# MOTO1.net
KiCad netlist of a schematic drawn in Altium Designer
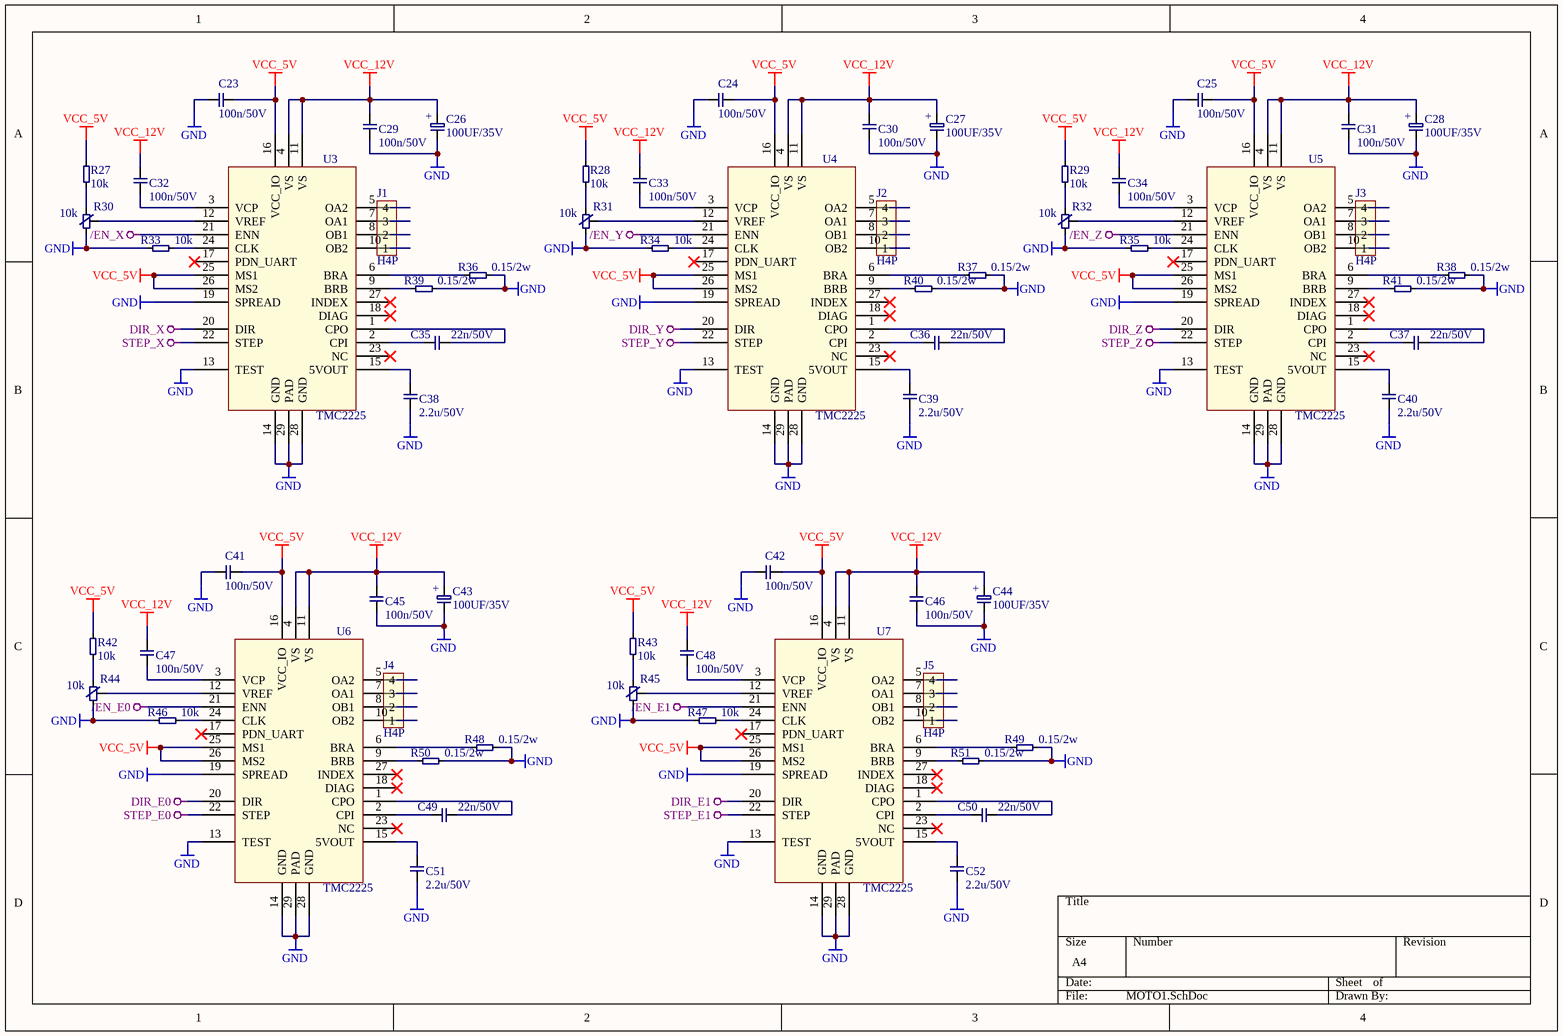
[diagram p0: MOTO1.SchDoc]

(export (version "E")
  (design (tool "Eeschema 10.0.6"))
  (components
    (comp (ref "C23")
      (value "100n/50V")
      (footprint "C0603(1608)")
      (libsource (lib "Fc_Integrated_Library") (part "Caps"))
    )
    (comp (ref "C24")
      (value "100n/50V")
      (footprint "C0603(1608)")
      (libsource (lib "Fc_Integrated_Library") (part "Caps"))
    )
    (comp (ref "C25")
      (value "100n/50V")
      (footprint "C0603(1608)")
      (libsource (lib "Fc_Integrated_Library") (part "Caps"))
    )
    (comp (ref "C26")
      (value "100UF/35V")
      (footprint "C6.3x7.7贴片铝电解电容")
      (libsource (lib "Fc_Integrated_Library") (part "Capsp"))
    )
    (comp (ref "C27")
      (value "100UF/35V")
      (footprint "C6.3x7.7贴片铝电解电容")
      (libsource (lib "Fc_Integrated_Library") (part "Capsp"))
    )
    (comp (ref "C28")
      (value "100UF/35V")
      (footprint "C6.3x7.7贴片铝电解电容")
      (libsource (lib "Fc_Integrated_Library") (part "Capsp"))
    )
    (comp (ref "C29")
      (value "100n/50V")
      (footprint "C0603(1608)")
      (libsource (lib "Fc_Integrated_Library") (part "Caps"))
    )
    (comp (ref "C30")
      (value "100n/50V")
      (footprint "C0603(1608)")
      (libsource (lib "Fc_Integrated_Library") (part "Caps"))
    )
    (comp (ref "C31")
      (value "100n/50V")
      (footprint "C0603(1608)")
      (libsource (lib "Fc_Integrated_Library") (part "Caps"))
    )
    (comp (ref "C32")
      (value "100n/50V")
      (footprint "C0603(1608)")
      (libsource (lib "Fc_Integrated_Library") (part "Caps"))
    )
    (comp (ref "C33")
      (value "100n/50V")
      (footprint "C0603(1608)")
      (libsource (lib "Fc_Integrated_Library") (part "Caps"))
    )
    (comp (ref "C34")
      (value "100n/50V")
      (footprint "C0603(1608)")
      (libsource (lib "Fc_Integrated_Library") (part "Caps"))
    )
    (comp (ref "C35")
      (value "22n/50V")
      (footprint "C0603(1608)")
      (libsource (lib "Fc_Integrated_Library") (part "Caps"))
    )
    (comp (ref "C36")
      (value "22n/50V")
      (footprint "C0603(1608)")
      (libsource (lib "Fc_Integrated_Library") (part "Caps"))
    )
    (comp (ref "C37")
      (value "22n/50V")
      (footprint "C0603(1608)")
      (libsource (lib "Fc_Integrated_Library") (part "Caps"))
    )
    (comp (ref "C38")
      (value "2.2u/50V")
      (footprint "C0805(2012)")
      (libsource (lib "Fc_Integrated_Library") (part "Caps"))
    )
    (comp (ref "C39")
      (value "2.2u/50V")
      (footprint "C0805(2012)")
      (libsource (lib "Fc_Integrated_Library") (part "Caps"))
    )
    (comp (ref "C40")
      (value "2.2u/50V")
      (footprint "C0805(2012)")
      (libsource (lib "Fc_Integrated_Library") (part "Caps"))
    )
    (comp (ref "C41")
      (value "100n/50V")
      (footprint "C0603(1608)")
      (libsource (lib "Fc_Integrated_Library") (part "Caps"))
    )
    (comp (ref "C42")
      (value "100n/50V")
      (footprint "C0603(1608)")
      (libsource (lib "Fc_Integrated_Library") (part "Caps"))
    )
    (comp (ref "C43")
      (value "100UF/35V")
      (footprint "C6.3x7.7贴片铝电解电容")
      (libsource (lib "Fc_Integrated_Library") (part "Capsp"))
    )
    (comp (ref "C44")
      (value "100UF/35V")
      (footprint "C6.3x7.7贴片铝电解电容")
      (libsource (lib "Fc_Integrated_Library") (part "Capsp"))
    )
    (comp (ref "C45")
      (value "100n/50V")
      (footprint "C0603(1608)")
      (libsource (lib "Fc_Integrated_Library") (part "Caps"))
    )
    (comp (ref "C46")
      (value "100n/50V")
      (footprint "C0603(1608)")
      (libsource (lib "Fc_Integrated_Library") (part "Caps"))
    )
    (comp (ref "C47")
      (value "100n/50V")
      (footprint "C0603(1608)")
      (libsource (lib "Fc_Integrated_Library") (part "Caps"))
    )
    (comp (ref "C48")
      (value "100n/50V")
      (footprint "C0603(1608)")
      (libsource (lib "Fc_Integrated_Library") (part "Caps"))
    )
    (comp (ref "C49")
      (value "22n/50V")
      (footprint "C0603(1608)")
      (libsource (lib "Fc_Integrated_Library") (part "Caps"))
    )
    (comp (ref "C50")
      (value "22n/50V")
      (footprint "C0603(1608)")
      (libsource (lib "Fc_Integrated_Library") (part "Caps"))
    )
    (comp (ref "C51")
      (value "2.2u/50V")
      (footprint "C0805(2012)")
      (libsource (lib "Fc_Integrated_Library") (part "Caps"))
    )
    (comp (ref "C52")
      (value "2.2u/50V")
      (footprint "C0805(2012)")
      (libsource (lib "Fc_Integrated_Library") (part "Caps"))
    )
    (comp (ref "J1")
      (value "H4P")
      (footprint "XH2.54(2.5mm)x4P")
      (libsource (lib "Fc_Integrated_Library") (part "H4P"))
    )
    (comp (ref "J2")
      (value "H4P")
      (footprint "XH2.54(2.5mm)x4P")
      (libsource (lib "Fc_Integrated_Library") (part "H4P"))
    )
    (comp (ref "J3")
      (value "H4P")
      (footprint "XH2.54(2.5mm)x4P")
      (libsource (lib "Fc_Integrated_Library") (part "H4P"))
    )
    (comp (ref "J4")
      (value "H4P")
      (footprint "XH2.54(2.5mm)x4P")
      (libsource (lib "Fc_Integrated_Library") (part "H4P"))
    )
    (comp (ref "J5")
      (value "H4P")
      (footprint "XH2.54(2.5mm)x4P")
      (libsource (lib "Fc_Integrated_Library") (part "H4P"))
    )
    (comp (ref "R27")
      (value "10k")
      (footprint "R0603(1608)")
      (libsource (lib "Fc_Integrated_Library") (part "Ress"))
    )
    (comp (ref "R28")
      (value "10k")
      (footprint "R0603(1608)")
      (libsource (lib "Fc_Integrated_Library") (part "Ress"))
    )
    (comp (ref "R29")
      (value "10k")
      (footprint "R0603(1608)")
      (libsource (lib "Fc_Integrated_Library") (part "Ress"))
    )
    (comp (ref "R30")
      (value "10k")
      (footprint "R3x3-贴片电位器")
      (libsource (lib "Fc_Integrated_Library") (part "Resc"))
    )
    (comp (ref "R31")
      (value "10k")
      (footprint "R3x3-贴片电位器")
      (libsource (lib "Fc_Integrated_Library") (part "Resc"))
    )
    (comp (ref "R32")
      (value "10k")
      (footprint "R3x3-贴片电位器")
      (libsource (lib "Fc_Integrated_Library") (part "Resc"))
    )
    (comp (ref "R33")
      (value "10k")
      (footprint "R0603(1608)")
      (libsource (lib "Fc_Integrated_Library") (part "Ress"))
    )
    (comp (ref "R34")
      (value "10k")
      (footprint "R0603(1608)")
      (libsource (lib "Fc_Integrated_Library") (part "Ress"))
    )
    (comp (ref "R35")
      (value "10k")
      (footprint "R0603(1608)")
      (libsource (lib "Fc_Integrated_Library") (part "Ress"))
    )
    (comp (ref "R36")
      (value "0.15/2w")
      (footprint "R2512")
      (libsource (lib "Fc_Integrated_Library") (part "Ress"))
    )
    (comp (ref "R37")
      (value "0.15/2w")
      (footprint "R2512")
      (libsource (lib "Fc_Integrated_Library") (part "Ress"))
    )
    (comp (ref "R38")
      (value "0.15/2w")
      (footprint "R2512")
      (libsource (lib "Fc_Integrated_Library") (part "Ress"))
    )
    (comp (ref "R39")
      (value "0.15/2w")
      (footprint "R2512")
      (libsource (lib "Fc_Integrated_Library") (part "Ress"))
    )
    (comp (ref "R40")
      (value "0.15/2w")
      (footprint "R2512")
      (libsource (lib "Fc_Integrated_Library") (part "Ress"))
    )
    (comp (ref "R41")
      (value "0.15/2w")
      (footprint "R2512")
      (libsource (lib "Fc_Integrated_Library") (part "Ress"))
    )
    (comp (ref "R42")
      (value "10k")
      (footprint "R0603(1608)")
      (libsource (lib "Fc_Integrated_Library") (part "Ress"))
    )
    (comp (ref "R43")
      (value "10k")
      (footprint "R0603(1608)")
      (libsource (lib "Fc_Integrated_Library") (part "Ress"))
    )
    (comp (ref "R44")
      (value "10k")
      (footprint "R3x3-贴片电位器")
      (libsource (lib "Fc_Integrated_Library") (part "Resc"))
    )
    (comp (ref "R45")
      (value "10k")
      (footprint "R3x3-贴片电位器")
      (libsource (lib "Fc_Integrated_Library") (part "Resc"))
    )
    (comp (ref "R46")
      (value "10k")
      (footprint "R0603(1608)")
      (libsource (lib "Fc_Integrated_Library") (part "Ress"))
    )
    (comp (ref "R47")
      (value "10k")
      (footprint "R0603(1608)")
      (libsource (lib "Fc_Integrated_Library") (part "Ress"))
    )
    (comp (ref "R48")
      (value "0.15/2w")
      (footprint "R2512")
      (libsource (lib "Fc_Integrated_Library") (part "Ress"))
    )
    (comp (ref "R49")
      (value "0.15/2w")
      (footprint "R2512")
      (libsource (lib "Fc_Integrated_Library") (part "Ress"))
    )
    (comp (ref "R50")
      (value "0.15/2w")
      (footprint "R2512")
      (libsource (lib "Fc_Integrated_Library") (part "Ress"))
    )
    (comp (ref "R51")
      (value "0.15/2w")
      (footprint "R2512")
      (libsource (lib "Fc_Integrated_Library") (part "Ress"))
    )
    (comp (ref "U3")
      (value "TMC2225")
      (footprint "HTSSOP28")
      (libsource (lib "Fc_Integrated_Library") (part "TMC2225"))
    )
    (comp (ref "U4")
      (value "TMC2225")
      (footprint "HTSSOP28")
      (libsource (lib "Fc_Integrated_Library") (part "TMC2225"))
    )
    (comp (ref "U5")
      (value "TMC2225")
      (footprint "HTSSOP28")
      (libsource (lib "Fc_Integrated_Library") (part "TMC2225"))
    )
    (comp (ref "U6")
      (value "TMC2225")
      (footprint "HTSSOP28")
      (libsource (lib "Fc_Integrated_Library") (part "TMC2225"))
    )
    (comp (ref "U7")
      (value "TMC2225")
      (footprint "HTSSOP28")
      (libsource (lib "Fc_Integrated_Library") (part "TMC2225"))
    )
  )
  (nets
    (net (code "1") (name "DIR_E0") (class "Default")
      (node (ref "U6") (pin "20") (pinfunction "DIR_20") (pintype "passive"))
    )
    (net (code "2") (name "DIR_E1") (class "Default")
      (node (ref "U7") (pin "20") (pinfunction "DIR_20") (pintype "passive"))
    )
    (net (code "3") (name "DIR_X") (class "Default")
      (node (ref "U3") (pin "20") (pinfunction "DIR_20") (pintype "passive"))
    )
    (net (code "4") (name "DIR_Y") (class "Default")
      (node (ref "U4") (pin "20") (pinfunction "DIR_20") (pintype "passive"))
    )
    (net (code "5") (name "DIR_Z") (class "Default")
      (node (ref "U5") (pin "20") (pinfunction "DIR_20") (pintype "passive"))
    )
    (net (code "6") (name "GND") (class "Default")
      (node (ref "C23") (pin "2") (pinfunction "2_2") (pintype "passive"))
      (node (ref "C24") (pin "2") (pinfunction "2_2") (pintype "passive"))
      (node (ref "C25") (pin "2") (pinfunction "2_2") (pintype "passive"))
      (node (ref "C26") (pin "2") (pinfunction "2_2") (pintype "passive"))
      (node (ref "C27") (pin "2") (pinfunction "2_2") (pintype "passive"))
      (node (ref "C28") (pin "2") (pinfunction "2_2") (pintype "passive"))
      (node (ref "C29") (pin "2") (pinfunction "2_2") (pintype "passive"))
      (node (ref "C30") (pin "2") (pinfunction "2_2") (pintype "passive"))
      (node (ref "C31") (pin "2") (pinfunction "2_2") (pintype "passive"))
      (node (ref "C38") (pin "2") (pinfunction "2_2") (pintype "passive"))
      (node (ref "C39") (pin "2") (pinfunction "2_2") (pintype "passive"))
      (node (ref "C40") (pin "2") (pinfunction "2_2") (pintype "passive"))
      (node (ref "C41") (pin "2") (pinfunction "2_2") (pintype "passive"))
      (node (ref "C42") (pin "2") (pinfunction "2_2") (pintype "passive"))
      (node (ref "C43") (pin "2") (pinfunction "2_2") (pintype "passive"))
      (node (ref "C44") (pin "2") (pinfunction "2_2") (pintype "passive"))
      (node (ref "C45") (pin "2") (pinfunction "2_2") (pintype "passive"))
      (node (ref "C46") (pin "2") (pinfunction "2_2") (pintype "passive"))
      (node (ref "C51") (pin "2") (pinfunction "2_2") (pintype "passive"))
      (node (ref "C52") (pin "2") (pinfunction "2_2") (pintype "passive"))
      (node (ref "R30") (pin "3") (pinfunction "3_3") (pintype "passive"))
      (node (ref "R31") (pin "3") (pinfunction "3_3") (pintype "passive"))
      (node (ref "R32") (pin "3") (pinfunction "3_3") (pintype "passive"))
      (node (ref "R33") (pin "2") (pinfunction "2_2") (pintype "passive"))
      (node (ref "R34") (pin "2") (pinfunction "2_2") (pintype "passive"))
      (node (ref "R35") (pin "2") (pinfunction "2_2") (pintype "passive"))
      (node (ref "R36") (pin "1") (pinfunction "1_1") (pintype "passive"))
      (node (ref "R37") (pin "1") (pinfunction "1_1") (pintype "passive"))
      (node (ref "R38") (pin "1") (pinfunction "1_1") (pintype "passive"))
      (node (ref "R39") (pin "1") (pinfunction "1_1") (pintype "passive"))
      (node (ref "R40") (pin "1") (pinfunction "1_1") (pintype "passive"))
      (node (ref "R41") (pin "1") (pinfunction "1_1") (pintype "passive"))
      (node (ref "R44") (pin "3") (pinfunction "3_3") (pintype "passive"))
      (node (ref "R45") (pin "3") (pinfunction "3_3") (pintype "passive"))
      (node (ref "R46") (pin "2") (pinfunction "2_2") (pintype "passive"))
      (node (ref "R47") (pin "2") (pinfunction "2_2") (pintype "passive"))
      (node (ref "R48") (pin "1") (pinfunction "1_1") (pintype "passive"))
      (node (ref "R49") (pin "1") (pinfunction "1_1") (pintype "passive"))
      (node (ref "R50") (pin "1") (pinfunction "1_1") (pintype "passive"))
      (node (ref "R51") (pin "1") (pinfunction "1_1") (pintype "passive"))
      (node (ref "U3") (pin "13") (pinfunction "TEST_13") (pintype "passive"))
      (node (ref "U3") (pin "14") (pinfunction "GND_14") (pintype "passive"))
      (node (ref "U3") (pin "19") (pinfunction "SPREAD_19") (pintype "passive"))
      (node (ref "U3") (pin "28") (pinfunction "GND_28") (pintype "passive"))
      (node (ref "U3") (pin "29") (pinfunction "PAD_29") (pintype "passive"))
      (node (ref "U4") (pin "13") (pinfunction "TEST_13") (pintype "passive"))
      (node (ref "U4") (pin "14") (pinfunction "GND_14") (pintype "passive"))
      (node (ref "U4") (pin "19") (pinfunction "SPREAD_19") (pintype "passive"))
      (node (ref "U4") (pin "28") (pinfunction "GND_28") (pintype "passive"))
      (node (ref "U4") (pin "29") (pinfunction "PAD_29") (pintype "passive"))
      (node (ref "U5") (pin "13") (pinfunction "TEST_13") (pintype "passive"))
      (node (ref "U5") (pin "14") (pinfunction "GND_14") (pintype "passive"))
      (node (ref "U5") (pin "19") (pinfunction "SPREAD_19") (pintype "passive"))
      (node (ref "U5") (pin "28") (pinfunction "GND_28") (pintype "passive"))
      (node (ref "U5") (pin "29") (pinfunction "PAD_29") (pintype "passive"))
      (node (ref "U6") (pin "13") (pinfunction "TEST_13") (pintype "passive"))
      (node (ref "U6") (pin "14") (pinfunction "GND_14") (pintype "passive"))
      (node (ref "U6") (pin "19") (pinfunction "SPREAD_19") (pintype "passive"))
      (node (ref "U6") (pin "28") (pinfunction "GND_28") (pintype "passive"))
      (node (ref "U6") (pin "29") (pinfunction "PAD_29") (pintype "passive"))
      (node (ref "U7") (pin "13") (pinfunction "TEST_13") (pintype "passive"))
      (node (ref "U7") (pin "14") (pinfunction "GND_14") (pintype "passive"))
      (node (ref "U7") (pin "19") (pinfunction "SPREAD_19") (pintype "passive"))
      (node (ref "U7") (pin "28") (pinfunction "GND_28") (pintype "passive"))
      (node (ref "U7") (pin "29") (pinfunction "PAD_29") (pintype "passive"))
    )
    (net (code "7") (name "Net-(R27-Pad1)") (class "Default")
      (node (ref "R27") (pin "1") (pinfunction "1_1") (pintype "passive"))
      (node (ref "R30") (pin "1") (pinfunction "1_1") (pintype "passive"))
    )
    (net (code "8") (name "Net-(R28-Pad1)") (class "Default")
      (node (ref "R28") (pin "1") (pinfunction "1_1") (pintype "passive"))
      (node (ref "R31") (pin "1") (pinfunction "1_1") (pintype "passive"))
    )
    (net (code "9") (name "Net-(R29-Pad1)") (class "Default")
      (node (ref "R29") (pin "1") (pinfunction "1_1") (pintype "passive"))
      (node (ref "R32") (pin "1") (pinfunction "1_1") (pintype "passive"))
    )
    (net (code "10") (name "Net-(R42-Pad1)") (class "Default")
      (node (ref "R42") (pin "1") (pinfunction "1_1") (pintype "passive"))
      (node (ref "R44") (pin "1") (pinfunction "1_1") (pintype "passive"))
    )
    (net (code "11") (name "Net-(R43-Pad1)") (class "Default")
      (node (ref "R43") (pin "1") (pinfunction "1_1") (pintype "passive"))
      (node (ref "R45") (pin "1") (pinfunction "1_1") (pintype "passive"))
    )
    (net (code "12") (name "Net-(U3-5VOUT)") (class "Default")
      (node (ref "C38") (pin "1") (pinfunction "1_1") (pintype "passive"))
      (node (ref "U3") (pin "15") (pinfunction "5VOUT_15") (pintype "passive"))
    )
    (net (code "13") (name "Net-(U3-BRA)") (class "Default")
      (node (ref "R36") (pin "2") (pinfunction "2_2") (pintype "passive"))
      (node (ref "U3") (pin "6") (pinfunction "BRA_6") (pintype "passive"))
    )
    (net (code "14") (name "Net-(U3-BRB)") (class "Default")
      (node (ref "R39") (pin "2") (pinfunction "2_2") (pintype "passive"))
      (node (ref "U3") (pin "9") (pinfunction "BRB_9") (pintype "passive"))
    )
    (net (code "15") (name "Net-(U3-CLK)") (class "Default")
      (node (ref "R33") (pin "1") (pinfunction "1_1") (pintype "passive"))
      (node (ref "U3") (pin "24") (pinfunction "CLK_24") (pintype "passive"))
    )
    (net (code "16") (name "Net-(U3-CPI)") (class "Default")
      (node (ref "C35") (pin "1") (pinfunction "1_1") (pintype "passive"))
      (node (ref "U3") (pin "2") (pinfunction "CPI_2") (pintype "passive"))
    )
    (net (code "17") (name "Net-(U3-CPO)") (class "Default")
      (node (ref "C35") (pin "2") (pinfunction "2_2") (pintype "passive"))
      (node (ref "U3") (pin "1") (pinfunction "CPO_1") (pintype "passive"))
    )
    (net (code "18") (name "Net-(U3-OA1)") (class "Default")
      (node (ref "J1") (pin "3") (pinfunction "3_3") (pintype "passive"))
      (node (ref "U3") (pin "7") (pinfunction "OA1_7") (pintype "passive"))
    )
    (net (code "19") (name "Net-(U3-OA2)") (class "Default")
      (node (ref "J1") (pin "4") (pinfunction "4_4") (pintype "passive"))
      (node (ref "U3") (pin "5") (pinfunction "OA2_5") (pintype "passive"))
    )
    (net (code "20") (name "Net-(U3-OB1)") (class "Default")
      (node (ref "J1") (pin "2") (pinfunction "2_2") (pintype "passive"))
      (node (ref "U3") (pin "8") (pinfunction "OB1_8") (pintype "passive"))
    )
    (net (code "21") (name "Net-(U3-OB2)") (class "Default")
      (node (ref "J1") (pin "1") (pinfunction "1_1") (pintype "passive"))
      (node (ref "U3") (pin "10") (pinfunction "OB2_10") (pintype "passive"))
    )
    (net (code "22") (name "Net-(U3-VCP)") (class "Default")
      (node (ref "C32") (pin "2") (pinfunction "2_2") (pintype "passive"))
      (node (ref "U3") (pin "3") (pinfunction "VCP_3") (pintype "passive"))
    )
    (net (code "23") (name "Net-(U3-VREF)") (class "Default")
      (node (ref "R30") (pin "2") (pinfunction "2_2") (pintype "passive"))
      (node (ref "U3") (pin "12") (pinfunction "VREF_12") (pintype "passive"))
    )
    (net (code "24") (name "Net-(U4-5VOUT)") (class "Default")
      (node (ref "C39") (pin "1") (pinfunction "1_1") (pintype "passive"))
      (node (ref "U4") (pin "15") (pinfunction "5VOUT_15") (pintype "passive"))
    )
    (net (code "25") (name "Net-(U4-BRA)") (class "Default")
      (node (ref "R37") (pin "2") (pinfunction "2_2") (pintype "passive"))
      (node (ref "U4") (pin "6") (pinfunction "BRA_6") (pintype "passive"))
    )
    (net (code "26") (name "Net-(U4-BRB)") (class "Default")
      (node (ref "R40") (pin "2") (pinfunction "2_2") (pintype "passive"))
      (node (ref "U4") (pin "9") (pinfunction "BRB_9") (pintype "passive"))
    )
    (net (code "27") (name "Net-(U4-CLK)") (class "Default")
      (node (ref "R34") (pin "1") (pinfunction "1_1") (pintype "passive"))
      (node (ref "U4") (pin "24") (pinfunction "CLK_24") (pintype "passive"))
    )
    (net (code "28") (name "Net-(U4-CPI)") (class "Default")
      (node (ref "C36") (pin "1") (pinfunction "1_1") (pintype "passive"))
      (node (ref "U4") (pin "2") (pinfunction "CPI_2") (pintype "passive"))
    )
    (net (code "29") (name "Net-(U4-CPO)") (class "Default")
      (node (ref "C36") (pin "2") (pinfunction "2_2") (pintype "passive"))
      (node (ref "U4") (pin "1") (pinfunction "CPO_1") (pintype "passive"))
    )
    (net (code "30") (name "Net-(U4-OA1)") (class "Default")
      (node (ref "J2") (pin "3") (pinfunction "3_3") (pintype "passive"))
      (node (ref "U4") (pin "7") (pinfunction "OA1_7") (pintype "passive"))
    )
    (net (code "31") (name "Net-(U4-OA2)") (class "Default")
      (node (ref "J2") (pin "4") (pinfunction "4_4") (pintype "passive"))
      (node (ref "U4") (pin "5") (pinfunction "OA2_5") (pintype "passive"))
    )
    (net (code "32") (name "Net-(U4-OB1)") (class "Default")
      (node (ref "J2") (pin "2") (pinfunction "2_2") (pintype "passive"))
      (node (ref "U4") (pin "8") (pinfunction "OB1_8") (pintype "passive"))
    )
    (net (code "33") (name "Net-(U4-OB2)") (class "Default")
      (node (ref "J2") (pin "1") (pinfunction "1_1") (pintype "passive"))
      (node (ref "U4") (pin "10") (pinfunction "OB2_10") (pintype "passive"))
    )
    (net (code "34") (name "Net-(U4-VCP)") (class "Default")
      (node (ref "C33") (pin "2") (pinfunction "2_2") (pintype "passive"))
      (node (ref "U4") (pin "3") (pinfunction "VCP_3") (pintype "passive"))
    )
    (net (code "35") (name "Net-(U4-VREF)") (class "Default")
      (node (ref "R31") (pin "2") (pinfunction "2_2") (pintype "passive"))
      (node (ref "U4") (pin "12") (pinfunction "VREF_12") (pintype "passive"))
    )
    (net (code "36") (name "Net-(U5-5VOUT)") (class "Default")
      (node (ref "C40") (pin "1") (pinfunction "1_1") (pintype "passive"))
      (node (ref "U5") (pin "15") (pinfunction "5VOUT_15") (pintype "passive"))
    )
    (net (code "37") (name "Net-(U5-BRA)") (class "Default")
      (node (ref "R38") (pin "2") (pinfunction "2_2") (pintype "passive"))
      (node (ref "U5") (pin "6") (pinfunction "BRA_6") (pintype "passive"))
    )
    (net (code "38") (name "Net-(U5-BRB)") (class "Default")
      (node (ref "R41") (pin "2") (pinfunction "2_2") (pintype "passive"))
      (node (ref "U5") (pin "9") (pinfunction "BRB_9") (pintype "passive"))
    )
    (net (code "39") (name "Net-(U5-CLK)") (class "Default")
      (node (ref "R35") (pin "1") (pinfunction "1_1") (pintype "passive"))
      (node (ref "U5") (pin "24") (pinfunction "CLK_24") (pintype "passive"))
    )
    (net (code "40") (name "Net-(U5-CPI)") (class "Default")
      (node (ref "C37") (pin "1") (pinfunction "1_1") (pintype "passive"))
      (node (ref "U5") (pin "2") (pinfunction "CPI_2") (pintype "passive"))
    )
    (net (code "41") (name "Net-(U5-CPO)") (class "Default")
      (node (ref "C37") (pin "2") (pinfunction "2_2") (pintype "passive"))
      (node (ref "U5") (pin "1") (pinfunction "CPO_1") (pintype "passive"))
    )
    (net (code "42") (name "Net-(U5-OA1)") (class "Default")
      (node (ref "J3") (pin "3") (pinfunction "3_3") (pintype "passive"))
      (node (ref "U5") (pin "7") (pinfunction "OA1_7") (pintype "passive"))
    )
    (net (code "43") (name "Net-(U5-OA2)") (class "Default")
      (node (ref "J3") (pin "4") (pinfunction "4_4") (pintype "passive"))
      (node (ref "U5") (pin "5") (pinfunction "OA2_5") (pintype "passive"))
    )
    (net (code "44") (name "Net-(U5-OB1)") (class "Default")
      (node (ref "J3") (pin "2") (pinfunction "2_2") (pintype "passive"))
      (node (ref "U5") (pin "8") (pinfunction "OB1_8") (pintype "passive"))
    )
    (net (code "45") (name "Net-(U5-OB2)") (class "Default")
      (node (ref "J3") (pin "1") (pinfunction "1_1") (pintype "passive"))
      (node (ref "U5") (pin "10") (pinfunction "OB2_10") (pintype "passive"))
    )
    (net (code "46") (name "Net-(U5-VCP)") (class "Default")
      (node (ref "C34") (pin "2") (pinfunction "2_2") (pintype "passive"))
      (node (ref "U5") (pin "3") (pinfunction "VCP_3") (pintype "passive"))
    )
    (net (code "47") (name "Net-(U5-VREF)") (class "Default")
      (node (ref "R32") (pin "2") (pinfunction "2_2") (pintype "passive"))
      (node (ref "U5") (pin "12") (pinfunction "VREF_12") (pintype "passive"))
    )
    (net (code "48") (name "Net-(U6-5VOUT)") (class "Default")
      (node (ref "C51") (pin "1") (pinfunction "1_1") (pintype "passive"))
      (node (ref "U6") (pin "15") (pinfunction "5VOUT_15") (pintype "passive"))
    )
    (net (code "49") (name "Net-(U6-BRA)") (class "Default")
      (node (ref "R48") (pin "2") (pinfunction "2_2") (pintype "passive"))
      (node (ref "U6") (pin "6") (pinfunction "BRA_6") (pintype "passive"))
    )
    (net (code "50") (name "Net-(U6-BRB)") (class "Default")
      (node (ref "R50") (pin "2") (pinfunction "2_2") (pintype "passive"))
      (node (ref "U6") (pin "9") (pinfunction "BRB_9") (pintype "passive"))
    )
    (net (code "51") (name "Net-(U6-CLK)") (class "Default")
      (node (ref "R46") (pin "1") (pinfunction "1_1") (pintype "passive"))
      (node (ref "U6") (pin "24") (pinfunction "CLK_24") (pintype "passive"))
    )
    (net (code "52") (name "Net-(U6-CPI)") (class "Default")
      (node (ref "C49") (pin "1") (pinfunction "1_1") (pintype "passive"))
      (node (ref "U6") (pin "2") (pinfunction "CPI_2") (pintype "passive"))
    )
    (net (code "53") (name "Net-(U6-CPO)") (class "Default")
      (node (ref "C49") (pin "2") (pinfunction "2_2") (pintype "passive"))
      (node (ref "U6") (pin "1") (pinfunction "CPO_1") (pintype "passive"))
    )
    (net (code "54") (name "Net-(U6-OA1)") (class "Default")
      (node (ref "J4") (pin "3") (pinfunction "3_3") (pintype "passive"))
      (node (ref "U6") (pin "7") (pinfunction "OA1_7") (pintype "passive"))
    )
    (net (code "55") (name "Net-(U6-OA2)") (class "Default")
      (node (ref "J4") (pin "4") (pinfunction "4_4") (pintype "passive"))
      (node (ref "U6") (pin "5") (pinfunction "OA2_5") (pintype "passive"))
    )
    (net (code "56") (name "Net-(U6-OB1)") (class "Default")
      (node (ref "J4") (pin "2") (pinfunction "2_2") (pintype "passive"))
      (node (ref "U6") (pin "8") (pinfunction "OB1_8") (pintype "passive"))
    )
    (net (code "57") (name "Net-(U6-OB2)") (class "Default")
      (node (ref "J4") (pin "1") (pinfunction "1_1") (pintype "passive"))
      (node (ref "U6") (pin "10") (pinfunction "OB2_10") (pintype "passive"))
    )
    (net (code "58") (name "Net-(U6-VCP)") (class "Default")
      (node (ref "C47") (pin "2") (pinfunction "2_2") (pintype "passive"))
      (node (ref "U6") (pin "3") (pinfunction "VCP_3") (pintype "passive"))
    )
    (net (code "59") (name "Net-(U6-VREF)") (class "Default")
      (node (ref "R44") (pin "2") (pinfunction "2_2") (pintype "passive"))
      (node (ref "U6") (pin "12") (pinfunction "VREF_12") (pintype "passive"))
    )
    (net (code "60") (name "Net-(U7-5VOUT)") (class "Default")
      (node (ref "C52") (pin "1") (pinfunction "1_1") (pintype "passive"))
      (node (ref "U7") (pin "15") (pinfunction "5VOUT_15") (pintype "passive"))
    )
    (net (code "61") (name "Net-(U7-BRA)") (class "Default")
      (node (ref "R49") (pin "2") (pinfunction "2_2") (pintype "passive"))
      (node (ref "U7") (pin "6") (pinfunction "BRA_6") (pintype "passive"))
    )
    (net (code "62") (name "Net-(U7-BRB)") (class "Default")
      (node (ref "R51") (pin "2") (pinfunction "2_2") (pintype "passive"))
      (node (ref "U7") (pin "9") (pinfunction "BRB_9") (pintype "passive"))
    )
    (net (code "63") (name "Net-(U7-CLK)") (class "Default")
      (node (ref "R47") (pin "1") (pinfunction "1_1") (pintype "passive"))
      (node (ref "U7") (pin "24") (pinfunction "CLK_24") (pintype "passive"))
    )
    (net (code "64") (name "Net-(U7-CPI)") (class "Default")
      (node (ref "C50") (pin "1") (pinfunction "1_1") (pintype "passive"))
      (node (ref "U7") (pin "2") (pinfunction "CPI_2") (pintype "passive"))
    )
    (net (code "65") (name "Net-(U7-CPO)") (class "Default")
      (node (ref "C50") (pin "2") (pinfunction "2_2") (pintype "passive"))
      (node (ref "U7") (pin "1") (pinfunction "CPO_1") (pintype "passive"))
    )
    (net (code "66") (name "Net-(U7-OA1)") (class "Default")
      (node (ref "J5") (pin "3") (pinfunction "3_3") (pintype "passive"))
      (node (ref "U7") (pin "7") (pinfunction "OA1_7") (pintype "passive"))
    )
    (net (code "67") (name "Net-(U7-OA2)") (class "Default")
      (node (ref "J5") (pin "4") (pinfunction "4_4") (pintype "passive"))
      (node (ref "U7") (pin "5") (pinfunction "OA2_5") (pintype "passive"))
    )
    (net (code "68") (name "Net-(U7-OB1)") (class "Default")
      (node (ref "J5") (pin "2") (pinfunction "2_2") (pintype "passive"))
      (node (ref "U7") (pin "8") (pinfunction "OB1_8") (pintype "passive"))
    )
    (net (code "69") (name "Net-(U7-OB2)") (class "Default")
      (node (ref "J5") (pin "1") (pinfunction "1_1") (pintype "passive"))
      (node (ref "U7") (pin "10") (pinfunction "OB2_10") (pintype "passive"))
    )
    (net (code "70") (name "Net-(U7-VCP)") (class "Default")
      (node (ref "C48") (pin "2") (pinfunction "2_2") (pintype "passive"))
      (node (ref "U7") (pin "3") (pinfunction "VCP_3") (pintype "passive"))
    )
    (net (code "71") (name "Net-(U7-VREF)") (class "Default")
      (node (ref "R45") (pin "2") (pinfunction "2_2") (pintype "passive"))
      (node (ref "U7") (pin "12") (pinfunction "VREF_12") (pintype "passive"))
    )
    (net (code "72") (name "STEP_E0") (class "Default")
      (node (ref "U6") (pin "22") (pinfunction "STEP_22") (pintype "passive"))
    )
    (net (code "73") (name "STEP_E1") (class "Default")
      (node (ref "U7") (pin "22") (pinfunction "STEP_22") (pintype "passive"))
    )
    (net (code "74") (name "STEP_X") (class "Default")
      (node (ref "U3") (pin "22") (pinfunction "STEP_22") (pintype "passive"))
    )
    (net (code "75") (name "STEP_Y") (class "Default")
      (node (ref "U4") (pin "22") (pinfunction "STEP_22") (pintype "passive"))
    )
    (net (code "76") (name "STEP_Z") (class "Default")
      (node (ref "U5") (pin "22") (pinfunction "STEP_22") (pintype "passive"))
    )
    (net (code "77") (name "VCC_5V") (class "Default")
      (node (ref "C23") (pin "1") (pinfunction "1_1") (pintype "passive"))
      (node (ref "C24") (pin "1") (pinfunction "1_1") (pintype "passive"))
      (node (ref "C25") (pin "1") (pinfunction "1_1") (pintype "passive"))
      (node (ref "C41") (pin "1") (pinfunction "1_1") (pintype "passive"))
      (node (ref "C42") (pin "1") (pinfunction "1_1") (pintype "passive"))
      (node (ref "R27") (pin "2") (pinfunction "2_2") (pintype "passive"))
      (node (ref "R28") (pin "2") (pinfunction "2_2") (pintype "passive"))
      (node (ref "R29") (pin "2") (pinfunction "2_2") (pintype "passive"))
      (node (ref "R42") (pin "2") (pinfunction "2_2") (pintype "passive"))
      (node (ref "R43") (pin "2") (pinfunction "2_2") (pintype "passive"))
      (node (ref "U3") (pin "16") (pinfunction "VCC_IO_16") (pintype "passive"))
      (node (ref "U3") (pin "25") (pinfunction "MS1_25") (pintype "passive"))
      (node (ref "U3") (pin "26") (pinfunction "MS2_26") (pintype "passive"))
      (node (ref "U4") (pin "16") (pinfunction "VCC_IO_16") (pintype "passive"))
      (node (ref "U4") (pin "25") (pinfunction "MS1_25") (pintype "passive"))
      (node (ref "U4") (pin "26") (pinfunction "MS2_26") (pintype "passive"))
      (node (ref "U5") (pin "16") (pinfunction "VCC_IO_16") (pintype "passive"))
      (node (ref "U5") (pin "25") (pinfunction "MS1_25") (pintype "passive"))
      (node (ref "U5") (pin "26") (pinfunction "MS2_26") (pintype "passive"))
      (node (ref "U6") (pin "16") (pinfunction "VCC_IO_16") (pintype "passive"))
      (node (ref "U6") (pin "25") (pinfunction "MS1_25") (pintype "passive"))
      (node (ref "U6") (pin "26") (pinfunction "MS2_26") (pintype "passive"))
      (node (ref "U7") (pin "16") (pinfunction "VCC_IO_16") (pintype "passive"))
      (node (ref "U7") (pin "25") (pinfunction "MS1_25") (pintype "passive"))
      (node (ref "U7") (pin "26") (pinfunction "MS2_26") (pintype "passive"))
    )
    (net (code "78") (name "VCC_12V") (class "Default")
      (node (ref "C26") (pin "1") (pinfunction "1_1") (pintype "passive"))
      (node (ref "C27") (pin "1") (pinfunction "1_1") (pintype "passive"))
      (node (ref "C28") (pin "1") (pinfunction "1_1") (pintype "passive"))
      (node (ref "C29") (pin "1") (pinfunction "1_1") (pintype "passive"))
      (node (ref "C30") (pin "1") (pinfunction "1_1") (pintype "passive"))
      (node (ref "C31") (pin "1") (pinfunction "1_1") (pintype "passive"))
      (node (ref "C32") (pin "1") (pinfunction "1_1") (pintype "passive"))
      (node (ref "C33") (pin "1") (pinfunction "1_1") (pintype "passive"))
      (node (ref "C34") (pin "1") (pinfunction "1_1") (pintype "passive"))
      (node (ref "C43") (pin "1") (pinfunction "1_1") (pintype "passive"))
      (node (ref "C44") (pin "1") (pinfunction "1_1") (pintype "passive"))
      (node (ref "C45") (pin "1") (pinfunction "1_1") (pintype "passive"))
      (node (ref "C46") (pin "1") (pinfunction "1_1") (pintype "passive"))
      (node (ref "C47") (pin "1") (pinfunction "1_1") (pintype "passive"))
      (node (ref "C48") (pin "1") (pinfunction "1_1") (pintype "passive"))
      (node (ref "U3") (pin "11") (pinfunction "VS_11") (pintype "passive"))
      (node (ref "U3") (pin "4") (pinfunction "VS_4") (pintype "passive"))
      (node (ref "U4") (pin "11") (pinfunction "VS_11") (pintype "passive"))
      (node (ref "U4") (pin "4") (pinfunction "VS_4") (pintype "passive"))
      (node (ref "U5") (pin "11") (pinfunction "VS_11") (pintype "passive"))
      (node (ref "U5") (pin "4") (pinfunction "VS_4") (pintype "passive"))
      (node (ref "U6") (pin "11") (pinfunction "VS_11") (pintype "passive"))
      (node (ref "U6") (pin "4") (pinfunction "VS_4") (pintype "passive"))
      (node (ref "U7") (pin "11") (pinfunction "VS_11") (pintype "passive"))
      (node (ref "U7") (pin "4") (pinfunction "VS_4") (pintype "passive"))
    )
    (net (code "79") (name "unconnected-(U3-DIAG-Pad18)") (class "Default")
      (node (ref "U3") (pin "18") (pinfunction "DIAG_18") (pintype "passive+no_connect"))
    )
    (net (code "80") (name "unconnected-(U3-INDEX-Pad27)") (class "Default")
      (node (ref "U3") (pin "27") (pinfunction "INDEX_27") (pintype "passive+no_connect"))
    )
    (net (code "81") (name "unconnected-(U3-NC-Pad23)") (class "Default")
      (node (ref "U3") (pin "23") (pinfunction "NC_23") (pintype "passive+no_connect"))
    )
    (net (code "82") (name "unconnected-(U3-PDN_UART-Pad17)") (class "Default")
      (node (ref "U3") (pin "17") (pinfunction "PDN_UART_17") (pintype "passive+no_connect"))
    )
    (net (code "83") (name "unconnected-(U4-DIAG-Pad18)") (class "Default")
      (node (ref "U4") (pin "18") (pinfunction "DIAG_18") (pintype "passive+no_connect"))
    )
    (net (code "84") (name "unconnected-(U4-INDEX-Pad27)") (class "Default")
      (node (ref "U4") (pin "27") (pinfunction "INDEX_27") (pintype "passive+no_connect"))
    )
    (net (code "85") (name "unconnected-(U4-NC-Pad23)") (class "Default")
      (node (ref "U4") (pin "23") (pinfunction "NC_23") (pintype "passive+no_connect"))
    )
    (net (code "86") (name "unconnected-(U4-PDN_UART-Pad17)") (class "Default")
      (node (ref "U4") (pin "17") (pinfunction "PDN_UART_17") (pintype "passive+no_connect"))
    )
    (net (code "87") (name "unconnected-(U5-DIAG-Pad18)") (class "Default")
      (node (ref "U5") (pin "18") (pinfunction "DIAG_18") (pintype "passive+no_connect"))
    )
    (net (code "88") (name "unconnected-(U5-INDEX-Pad27)") (class "Default")
      (node (ref "U5") (pin "27") (pinfunction "INDEX_27") (pintype "passive+no_connect"))
    )
    (net (code "89") (name "unconnected-(U5-NC-Pad23)") (class "Default")
      (node (ref "U5") (pin "23") (pinfunction "NC_23") (pintype "passive+no_connect"))
    )
    (net (code "90") (name "unconnected-(U5-PDN_UART-Pad17)") (class "Default")
      (node (ref "U5") (pin "17") (pinfunction "PDN_UART_17") (pintype "passive+no_connect"))
    )
    (net (code "91") (name "unconnected-(U6-DIAG-Pad18)") (class "Default")
      (node (ref "U6") (pin "18") (pinfunction "DIAG_18") (pintype "passive+no_connect"))
    )
    (net (code "92") (name "unconnected-(U6-INDEX-Pad27)") (class "Default")
      (node (ref "U6") (pin "27") (pinfunction "INDEX_27") (pintype "passive+no_connect"))
    )
    (net (code "93") (name "unconnected-(U6-NC-Pad23)") (class "Default")
      (node (ref "U6") (pin "23") (pinfunction "NC_23") (pintype "passive+no_connect"))
    )
    (net (code "94") (name "unconnected-(U6-PDN_UART-Pad17)") (class "Default")
      (node (ref "U6") (pin "17") (pinfunction "PDN_UART_17") (pintype "passive+no_connect"))
    )
    (net (code "95") (name "unconnected-(U7-DIAG-Pad18)") (class "Default")
      (node (ref "U7") (pin "18") (pinfunction "DIAG_18") (pintype "passive+no_connect"))
    )
    (net (code "96") (name "unconnected-(U7-INDEX-Pad27)") (class "Default")
      (node (ref "U7") (pin "27") (pinfunction "INDEX_27") (pintype "passive+no_connect"))
    )
    (net (code "97") (name "unconnected-(U7-NC-Pad23)") (class "Default")
      (node (ref "U7") (pin "23") (pinfunction "NC_23") (pintype "passive+no_connect"))
    )
    (net (code "98") (name "unconnected-(U7-PDN_UART-Pad17)") (class "Default")
      (node (ref "U7") (pin "17") (pinfunction "PDN_UART_17") (pintype "passive+no_connect"))
    )
    (net (code "99") (name "{slash}EN_E0") (class "Default")
      (node (ref "U6") (pin "21") (pinfunction "ENN_21") (pintype "passive"))
    )
    (net (code "100") (name "{slash}EN_E1") (class "Default")
      (node (ref "U7") (pin "21") (pinfunction "ENN_21") (pintype "passive"))
    )
    (net (code "101") (name "{slash}EN_X") (class "Default")
      (node (ref "U3") (pin "21") (pinfunction "ENN_21") (pintype "passive"))
    )
    (net (code "102") (name "{slash}EN_Y") (class "Default")
      (node (ref "U4") (pin "21") (pinfunction "ENN_21") (pintype "passive"))
    )
    (net (code "103") (name "{slash}EN_Z") (class "Default")
      (node (ref "U5") (pin "21") (pinfunction "ENN_21") (pintype "passive"))
    )
  )
)
